# 30to50V-24V.net
KiCad netlist of a schematic drawn in Altium Designer
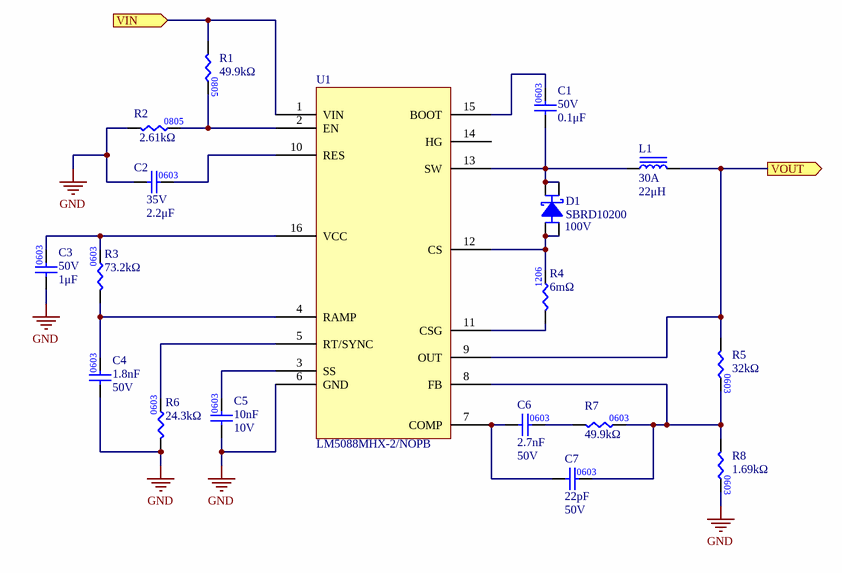
[diagram p0: 30to50V-24V.SchDoc]

(export (version "E")
  (design (tool "Eeschema 10.0.6"))
  (components
    (comp (ref "C1")
      (value "0.1μF")
      (footprint "CAP0603")
      (description "CAP CER 0.1UF 50V X7R 0603")
      (fields (field (name "VOLTAGE RATING") "50V") (field (name "Comment") "CAP_0.1uF_50V_0603"))
      (libsource (lib "UWRT_Schematic_Library_2020") (part "CAP_0.1uF_50V_0603"))
    )
    (comp (ref "C2")
      (value "2.2μF")
      (footprint "CAP0603")
      (description "CAP CER 2.2UF 35V X5R 0603")
      (fields (field (name "VOLTAGE RATING") "35V") (field (name "Comment") "CAP_2.2uF_35V_0603"))
      (libsource (lib "UWRT_Schematic_Library_2020") (part "CAP_2.2uF_35V_0603"))
    )
    (comp (ref "C3")
      (value "1μF")
      (footprint "CAP0603")
      (description "CAP CER 1UF 50V X6S 0603")
      (fields (field (name "VOLTAGE RATING") "50V") (field (name "Comment") "CAP_1uF_50V_0603"))
      (libsource (lib "UWRT_Schematic_Library_2020") (part "CAP_1uF_50V_0603"))
    )
    (comp (ref "C4")
      (value "1.8nF")
      (footprint "CAP0603")
      (description "CAP CER 1800PF 50V C0G/NP0 0603")
      (fields (field (name "VOLTAGE RATING") "50V") (field (name "Comment") "CAP_1.8nF_50V_0603"))
      (libsource (lib "UWRT_Schematic_Library_2020") (part "CAP_1.8nF_50V_0603"))
    )
    (comp (ref "C5")
      (value "10nF")
      (footprint "CAP0603")
      (description "CAP CER 10000PF 25V C0G 0603")
      (fields (field (name "VOLTAGE RATING") "10V") (field (name "Comment") "CAP_10nF_25V_0603"))
      (libsource (lib "UWRT_Schematic_Library_2020") (part "CAP_10nF_25V_0603"))
    )
    (comp (ref "C6")
      (value "2.7nF")
      (footprint "CAP0603")
      (description "CAP CER 2700PF 50V X7R 0603")
      (fields (field (name "VOLTAGE RATING") "50V") (field (name "Comment") "CAP_2.7nF_50V_0603"))
      (libsource (lib "UWRT_Schematic_Library_2020") (part "CAP_2.7nF_50V_0603"))
    )
    (comp (ref "C7")
      (value "22pF")
      (footprint "CAP0603")
      (description "CAP CER 22PF 50V C0G/NPO 0603")
      (fields (field (name "VOLTAGE RATING") "50V") (field (name "Comment") "CAP_22pF_50V_0603"))
      (libsource (lib "UWRT_Schematic_Library_2020") (part "CAP_22pF_50V_0603"))
    )
    (comp (ref "D1")
      (value "DIO_SCHOTTKY_100V_5.5A")
      (footprint "D-PAK")
      (description "DIODE SCHOTTKY 200V 10A DPAK")
      (fields (field (name "MANUFACTURER PART NUMBER 1") "SBRD10200") (field (name "VR (MAX)") "100V"))
      (libsource (lib "UWRT_Schematic_Library_2020") (part "DIO_SCHOTTKY_200V_10A"))
    )
    (comp (ref "L1")
      (value "IND_22uH_30A")
      (footprint "IND_VISHAY_IHLP6767GZ51")
      (description "FIXED IND 22UH 30A 2.4 MOHM SMD")
      (fields (field (name "CURRENT RATING") "30A") (field (name "INDUCTANCE") "22μH"))
      (libsource (lib "UWRT_Schematic_Library_2020") (part "IND_22uH_30A"))
    )
    (comp (ref "R1")
      (value "49.9kΩ")
      (footprint "RES0805")
      (description "RES 49.9K OHM 1% 1/8W 0805")
      (fields (field (name "LCSC PART #") "C17719") (field (name "Comment") "RES_49.9kΩ_0805_1%"))
      (libsource (lib "UWRT_Schematic_Library_2020") (part "RES_49.9kΩ_0805_1%"))
    )
    (comp (ref "R2")
      (value "2.61kΩ")
      (footprint "RES0805")
      (description "RES 2.61K OHM 1% 1/8W 0805")
      (fields (field (name "Comment") "RES_2.61kΩ_0805_1%"))
      (libsource (lib "UWRT_Schematic_Library_2020") (part "RES_2.61kΩ_0805_1%"))
    )
    (comp (ref "R3")
      (value "73.2kΩ")
      (footprint "RES0603")
      (description "RES 73.2K OHM 1% 1/10W 0603")
      (fields (field (name "POWER") "0.1W") (field (name "TOLERANCE") "1%"))
      (libsource (lib "UWRT_Schematic_Library_2020") (part "RES_73.2kΩ_0603_1%"))
    )
    (comp (ref "R4")
      (value "6mΩ")
      (footprint "RES1206")
      (description "RES 0.006 OHM 1% 1W 1206")
      (fields (field (name "Comment") "RES_0.006Ω_1206_1%"))
      (libsource (lib "UWRT_Schematic_Library_2020") (part "RES_0.006Ω_1206_1%"))
    )
    (comp (ref "R5")
      (value "32kΩ")
      (footprint "RES0603")
      (description "RES SMD 32K OHM 0.1% 1/10W 0603")
      (fields (field (name "Comment") "RES_32KΩ_0603_0.1%"))
      (libsource (lib "UWRT_Schematic_Library_2020") (part "RES_32KΩ_0603_0.1%"))
    )
    (comp (ref "R6")
      (value "24.3kΩ")
      (footprint "RES0603")
      (description "RES 24.3K OHM 1% 1/10W 0603")
      (fields (field (name "POWER") "0.1W") (field (name "TOLERANCE") "1%"))
      (libsource (lib "UWRT_Schematic_Library_2020") (part "RES_24.3kΩ_0603_1%"))
    )
    (comp (ref "R7")
      (value "49.9kΩ")
      (footprint "RES0603")
      (description "RES 49.9K OHM 1% 1/10W 0603")
      (fields (field (name "Comment") "RES_49.9kΩ_0603_1%"))
      (libsource (lib "UWRT_Schematic_Library_2020") (part "RES_49.9kΩ_0603_1%"))
    )
    (comp (ref "R8")
      (value "1.69kΩ")
      (footprint "RES0603")
      (description "RES 1.69K OHM 1% 1/10W 0603")
      (fields (field (name "Comment") "RES_1.69kΩ_0603_1%"))
      (libsource (lib "UWRT_Schematic_Library_2020") (part "RES_1.69kΩ_0603_1%"))
    )
    (comp (ref "U1")
      (value "LM5088")
      (description "IC REG CTRLR BUCK 16HTSSOP")
      (fields (field (name "MANUFACTURER PART NUMBER 1") "LM5088MHX-2/NOPB"))
      (libsource (lib "UWRT_Schematic_Library_2020") (part "LM5088MHX-2/NOPB"))
    )
  )
  (nets
    (net (code "1") (name "/VIN") (class "Default")
      (node (ref "R1") (pin "1") (pinfunction "1_1") (pintype "passive"))
      (node (ref "U1") (pin "1") (pinfunction "VIN_1") (pintype "passive"))
    )
    (net (code "2") (name "/VOUT") (class "Default")
      (node (ref "L1") (pin "2") (pinfunction "2_2") (pintype "passive"))
      (node (ref "R5") (pin "1") (pinfunction "1_1") (pintype "passive"))
      (node (ref "U1") (pin "9") (pinfunction "OUT_9") (pintype "passive"))
    )
    (net (code "3") (name "GND") (class "Default")
      (node (ref "C2") (pin "1") (pinfunction "1_1") (pintype "passive"))
      (node (ref "C3") (pin "1") (pinfunction "1_1") (pintype "passive"))
      (node (ref "C4") (pin "1") (pinfunction "1_1") (pintype "passive"))
      (node (ref "C5") (pin "1") (pinfunction "1_1") (pintype "passive"))
      (node (ref "R2") (pin "1") (pinfunction "1_1") (pintype "passive"))
      (node (ref "R6") (pin "1") (pinfunction "1_1") (pintype "passive"))
      (node (ref "R8") (pin "2") (pinfunction "2_2") (pintype "passive"))
      (node (ref "U1") (pin "6") (pinfunction "GND_6") (pintype "passive"))
    )
    (net (code "4") (name "Net-(C6-Pad2)") (class "Default")
      (node (ref "C6") (pin "2") (pinfunction "2_2") (pintype "passive"))
      (node (ref "R7") (pin "1") (pinfunction "1_1") (pintype "passive"))
    )
    (net (code "5") (name "Net-(U1-BOOT)") (class "Default")
      (node (ref "C1") (pin "2") (pinfunction "2_2") (pintype "passive"))
      (node (ref "U1") (pin "15") (pinfunction "BOOT_15") (pintype "passive"))
    )
    (net (code "6") (name "Net-(U1-COMP)") (class "Default")
      (node (ref "C6") (pin "1") (pinfunction "1_1") (pintype "passive"))
      (node (ref "C7") (pin "1") (pinfunction "1_1") (pintype "passive"))
      (node (ref "U1") (pin "7") (pinfunction "COMP_7") (pintype "passive"))
    )
    (net (code "7") (name "Net-(U1-CS)") (class "Default")
      (node (ref "D1") (pin "1") (pinfunction "Anode_1") (pintype "passive"))
      (node (ref "D1") (pin "3") (pinfunction "Anode_3") (pintype "passive"))
      (node (ref "R4") (pin "2") (pinfunction "2_2") (pintype "passive"))
      (node (ref "U1") (pin "12") (pinfunction "CS_12") (pintype "passive"))
    )
    (net (code "8") (name "Net-(U1-CSG)") (class "Default")
      (node (ref "R4") (pin "1") (pinfunction "1_1") (pintype "passive"))
      (node (ref "U1") (pin "11") (pinfunction "CSG_11") (pintype "passive"))
    )
    (net (code "9") (name "Net-(U1-EN)") (class "Default")
      (node (ref "R1") (pin "2") (pinfunction "2_2") (pintype "passive"))
      (node (ref "R2") (pin "2") (pinfunction "2_2") (pintype "passive"))
      (node (ref "U1") (pin "2") (pinfunction "EN_2") (pintype "passive"))
    )
    (net (code "10") (name "Net-(U1-FB)") (class "Default")
      (node (ref "C7") (pin "2") (pinfunction "2_2") (pintype "passive"))
      (node (ref "R5") (pin "2") (pinfunction "2_2") (pintype "passive"))
      (node (ref "R7") (pin "2") (pinfunction "2_2") (pintype "passive"))
      (node (ref "R8") (pin "1") (pinfunction "1_1") (pintype "passive"))
      (node (ref "U1") (pin "8") (pinfunction "FB_8") (pintype "passive"))
    )
    (net (code "11") (name "Net-(U1-RAMP)") (class "Default")
      (node (ref "C4") (pin "2") (pinfunction "2_2") (pintype "passive"))
      (node (ref "R3") (pin "1") (pinfunction "1_1") (pintype "passive"))
      (node (ref "U1") (pin "4") (pinfunction "RAMP_4") (pintype "passive"))
    )
    (net (code "12") (name "Net-(U1-RES)") (class "Default")
      (node (ref "C2") (pin "2") (pinfunction "2_2") (pintype "passive"))
      (node (ref "U1") (pin "10") (pinfunction "RES_10") (pintype "passive"))
    )
    (net (code "13") (name "Net-(U1-RT{slash}SYNC)") (class "Default")
      (node (ref "R6") (pin "2") (pinfunction "2_2") (pintype "passive"))
      (node (ref "U1") (pin "5") (pinfunction "RT/SYNC_5") (pintype "passive"))
    )
    (net (code "14") (name "Net-(U1-SS)") (class "Default")
      (node (ref "C5") (pin "2") (pinfunction "2_2") (pintype "passive"))
      (node (ref "U1") (pin "3") (pinfunction "SS_3") (pintype "passive"))
    )
    (net (code "15") (name "Net-(U1-SW)") (class "Default")
      (node (ref "C1") (pin "1") (pinfunction "1_1") (pintype "passive"))
      (node (ref "D1") (pin "2") (pinfunction "Cathode_2") (pintype "passive"))
      (node (ref "D1") (pin "4") (pinfunction "Cathode_4") (pintype "passive"))
      (node (ref "L1") (pin "1") (pinfunction "1_1") (pintype "passive"))
      (node (ref "U1") (pin "13") (pinfunction "SW_13") (pintype "passive"))
    )
    (net (code "16") (name "Net-(U1-VCC)") (class "Default")
      (node (ref "C3") (pin "2") (pinfunction "2_2") (pintype "passive"))
      (node (ref "R3") (pin "2") (pinfunction "2_2") (pintype "passive"))
      (node (ref "U1") (pin "16") (pinfunction "VCC_16") (pintype "passive"))
    )
    (net (code "17") (name "unconnected-(U1-HG-Pad14)") (class "Default")
      (node (ref "U1") (pin "14") (pinfunction "HG_14") (pintype "passive"))
    )
  )
)
